# mem.net
KiCad netlist of a schematic drawn in Altium Designer
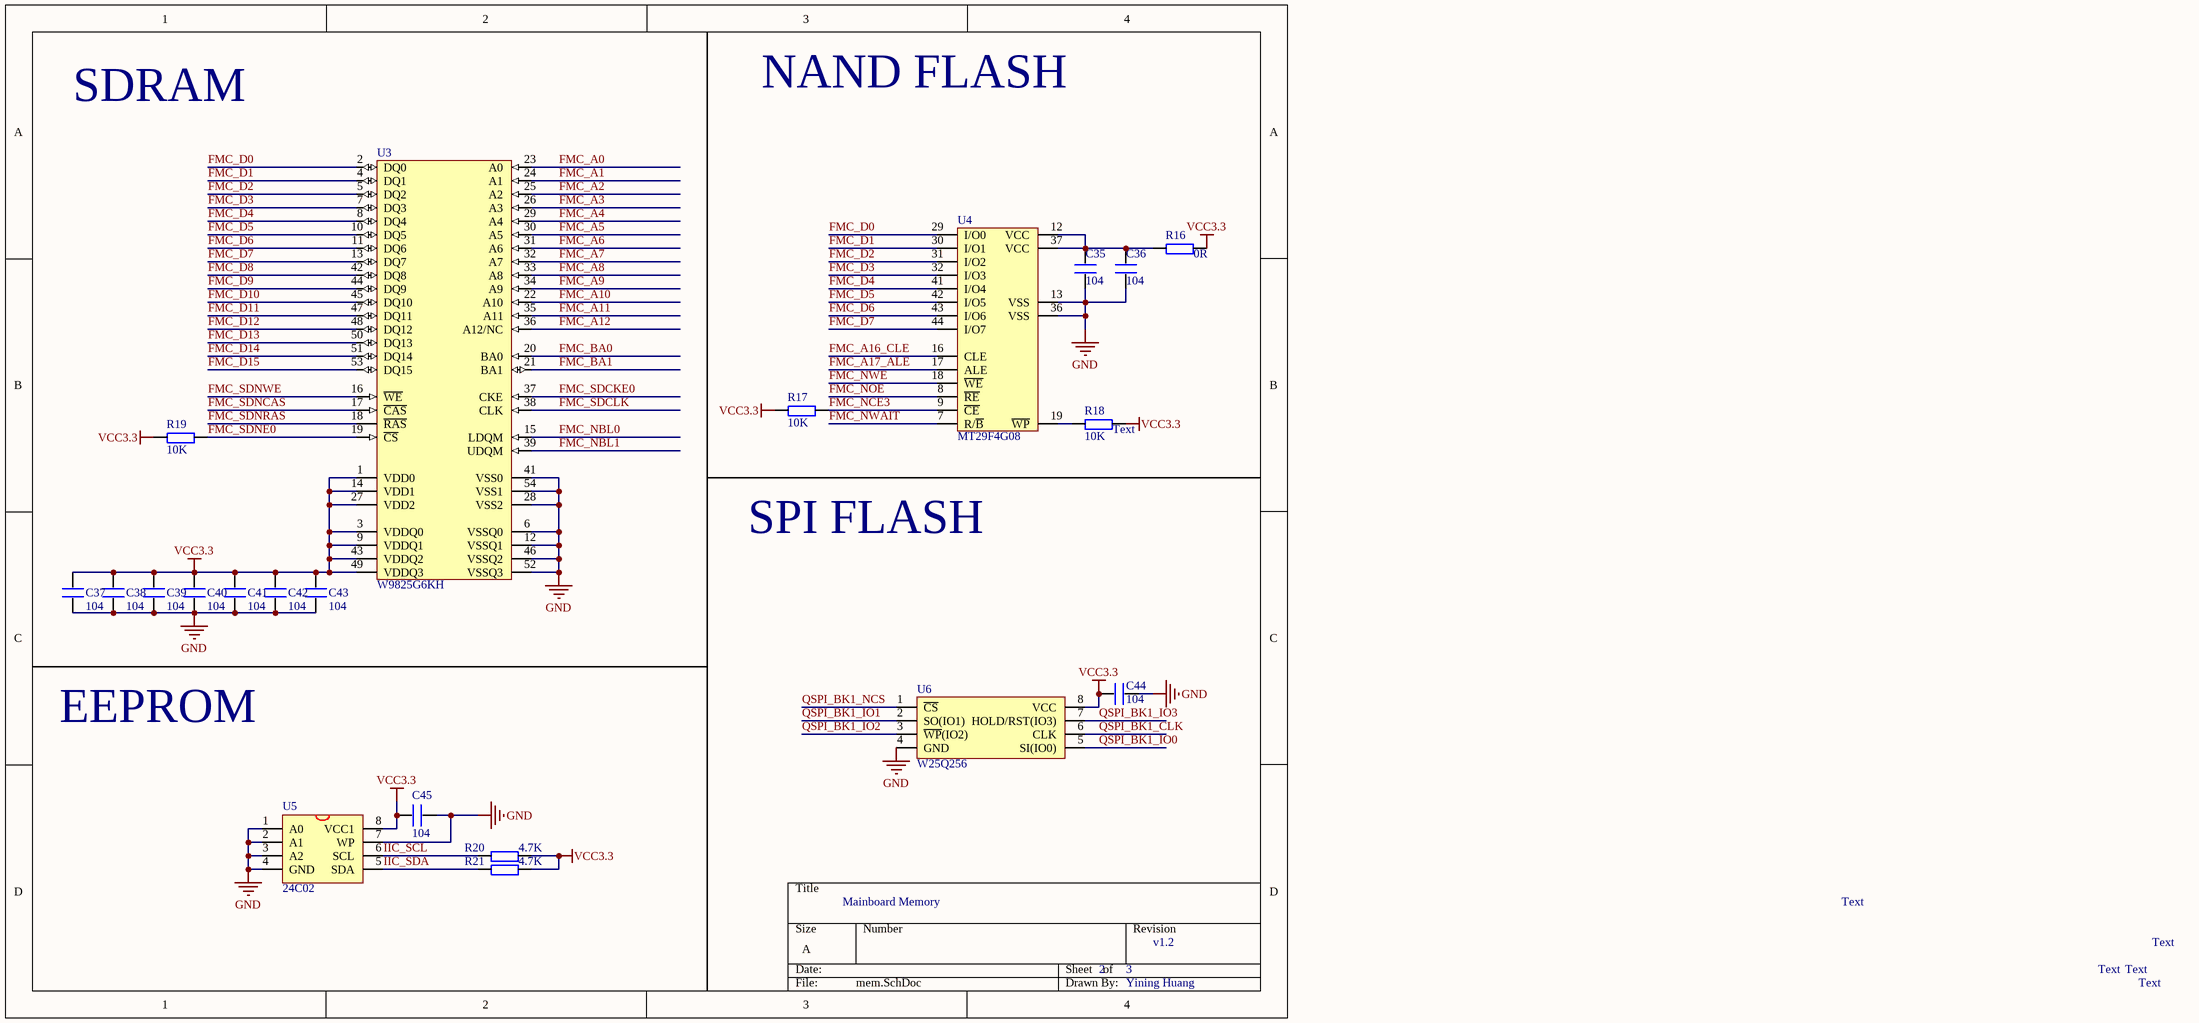
[diagram p0: mem.SchDoc]

(export (version "E")
  (design (tool "Eeschema 10.0.6"))
  (components
    (comp (ref "C35") (value "104") (footprint "0805") (libsource (lib "STM32F767核心板封装库") (part "C")))
    (comp (ref "C36") (value "104") (footprint "0805") (libsource (lib "STM32F767核心板封装库") (part "C")))
    (comp (ref "C37") (value "104") (footprint "0805") (libsource (lib "STM32F767核心板封装库") (part "C")))
    (comp (ref "C38") (value "104") (footprint "0805") (libsource (lib "STM32F767核心板封装库") (part "C")))
    (comp (ref "C39") (value "104") (footprint "0805") (libsource (lib "STM32F767核心板封装库") (part "C")))
    (comp (ref "C40") (value "104") (footprint "0805") (libsource (lib "STM32F767核心板封装库") (part "C")))
    (comp (ref "C41") (value "104") (footprint "0805") (libsource (lib "STM32F767核心板封装库") (part "C")))
    (comp (ref "C42") (value "104") (footprint "0805") (libsource (lib "STM32F767核心板封装库") (part "C")))
    (comp (ref "C43") (value "104") (footprint "0805") (libsource (lib "STM32F767核心板封装库") (part "C")))
    (comp (ref "C44") (value "104") (footprint "0805") (libsource (lib "STM32F767核心板封装库") (part "C")))
    (comp (ref "C45") (value "104") (footprint "0805") (libsource (lib "STM32F767核心板封装库") (part "C")))
    (comp (ref "R16") (value "0R") (footprint "0805") (libsource (lib "STM32F767核心板封装库") (part "R")))
    (comp (ref "R17") (value "10K") (footprint "0805") (libsource (lib "STM32F767核心板封装库") (part "R")))
    (comp (ref "R18") (value "10K") (footprint "0805") (libsource (lib "STM32F767核心板封装库") (part "R")))
    (comp (ref "R19") (value "10K") (footprint "0805") (libsource (lib "STM32F767核心板封装库") (part "R")))
    (comp (ref "R20") (value "4.7K") (footprint "0805") (libsource (lib "STM32F767核心板封装库") (part "R")))
    (comp (ref "R21") (value "4.7K") (footprint "0805") (libsource (lib "STM32F767核心板封装库") (part "R")))
    (comp (ref "U3")
      (value "W9825G6KH")
      (footprint "TSOP54")
      (description "32MB SDRAM")
      (libsource (lib "STM32F767核心板封装库") (part "IS42S16160B"))
    )
    (comp (ref "U4")
      (value "MT29F4G08")
      (footprint "TSOP48")
      (description "256MB NAND FLASH")
      (libsource (lib "STM32F767核心板封装库") (part "K9F2G08U0C"))
    )
    (comp (ref "U5")
      (value "24C02")
      (footprint "SOP-8")
      (description "EEPROM")
      (libsource (lib "STM32F767核心板封装库") (part "24C256"))
    )
    (comp (ref "U6")
      (value "W25Q256")
      (footprint "WSON8")
      (description "W25Q128")
      (libsource (lib "STM32F767核心板封装库") (part "W25Q128"))
    )
  )
  (nets
    (net (code "1") (name "/FMC_A0") (class "Default")
      (node (ref "U3") (pin "23") (pinfunction "A0_23") (pintype "input"))
    )
    (net (code "2") (name "/FMC_A1") (class "Default")
      (node (ref "U3") (pin "24") (pinfunction "A1_24") (pintype "input"))
    )
    (net (code "3") (name "/FMC_A2") (class "Default")
      (node (ref "U3") (pin "25") (pinfunction "A2_25") (pintype "input"))
    )
    (net (code "4") (name "/FMC_A3") (class "Default")
      (node (ref "U3") (pin "26") (pinfunction "A3_26") (pintype "input"))
    )
    (net (code "5") (name "/FMC_A4") (class "Default")
      (node (ref "U3") (pin "29") (pinfunction "A4_29") (pintype "input"))
    )
    (net (code "6") (name "/FMC_A5") (class "Default")
      (node (ref "U3") (pin "30") (pinfunction "A5_30") (pintype "input"))
    )
    (net (code "7") (name "/FMC_A6") (class "Default")
      (node (ref "U3") (pin "31") (pinfunction "A6_31") (pintype "input"))
    )
    (net (code "8") (name "/FMC_A7") (class "Default")
      (node (ref "U3") (pin "32") (pinfunction "A7_32") (pintype "input"))
    )
    (net (code "9") (name "/FMC_A8") (class "Default")
      (node (ref "U3") (pin "33") (pinfunction "A8_33") (pintype "input"))
    )
    (net (code "10") (name "/FMC_A9") (class "Default")
      (node (ref "U3") (pin "34") (pinfunction "A9_34") (pintype "input"))
    )
    (net (code "11") (name "/FMC_A10") (class "Default")
      (node (ref "U3") (pin "22") (pinfunction "A10_22") (pintype "input"))
    )
    (net (code "12") (name "/FMC_A11") (class "Default")
      (node (ref "U3") (pin "35") (pinfunction "A11_35") (pintype "input"))
    )
    (net (code "13") (name "/FMC_A12") (class "Default")
      (node (ref "U3") (pin "36") (pinfunction "A12/NC_36") (pintype "input"))
    )
    (net (code "14") (name "/FMC_A16_CLE") (class "Default")
      (node (ref "U4") (pin "16") (pinfunction "CLE_16") (pintype "passive"))
    )
    (net (code "15") (name "/FMC_A17_ALE") (class "Default")
      (node (ref "U4") (pin "17") (pinfunction "ALE_17") (pintype "passive"))
    )
    (net (code "16") (name "/FMC_BA0") (class "Default")
      (node (ref "U3") (pin "20") (pinfunction "BA0_20") (pintype "input"))
    )
    (net (code "17") (name "/FMC_BA1") (class "Default")
      (node (ref "U3") (pin "21") (pinfunction "BA1_21") (pintype "bidirectional"))
    )
    (net (code "18") (name "/FMC_D0") (class "Default")
      (node (ref "U3") (pin "2") (pinfunction "DQ0_2") (pintype "bidirectional"))
      (node (ref "U4") (pin "29") (pinfunction "I/O0_29") (pintype "passive"))
    )
    (net (code "19") (name "/FMC_D1") (class "Default")
      (node (ref "U3") (pin "4") (pinfunction "DQ1_4") (pintype "bidirectional"))
      (node (ref "U4") (pin "30") (pinfunction "I/O1_30") (pintype "passive"))
    )
    (net (code "20") (name "/FMC_D2") (class "Default")
      (node (ref "U3") (pin "5") (pinfunction "DQ2_5") (pintype "bidirectional"))
      (node (ref "U4") (pin "31") (pinfunction "I/O2_31") (pintype "passive"))
    )
    (net (code "21") (name "/FMC_D3") (class "Default")
      (node (ref "U3") (pin "7") (pinfunction "DQ3_7") (pintype "bidirectional"))
      (node (ref "U4") (pin "32") (pinfunction "I/O3_32") (pintype "passive"))
    )
    (net (code "22") (name "/FMC_D4") (class "Default")
      (node (ref "U3") (pin "8") (pinfunction "DQ4_8") (pintype "bidirectional"))
      (node (ref "U4") (pin "41") (pinfunction "I/O4_41") (pintype "passive"))
    )
    (net (code "23") (name "/FMC_D5") (class "Default")
      (node (ref "U3") (pin "10") (pinfunction "DQ5_10") (pintype "bidirectional"))
      (node (ref "U4") (pin "42") (pinfunction "I/O5_42") (pintype "passive"))
    )
    (net (code "24") (name "/FMC_D6") (class "Default")
      (node (ref "U3") (pin "11") (pinfunction "DQ6_11") (pintype "bidirectional"))
      (node (ref "U4") (pin "43") (pinfunction "I/O6_43") (pintype "passive"))
    )
    (net (code "25") (name "/FMC_D7") (class "Default")
      (node (ref "U3") (pin "13") (pinfunction "DQ7_13") (pintype "bidirectional"))
      (node (ref "U4") (pin "44") (pinfunction "I/O7_44") (pintype "passive"))
    )
    (net (code "26") (name "/FMC_D8") (class "Default")
      (node (ref "U3") (pin "42") (pinfunction "DQ8_42") (pintype "bidirectional"))
    )
    (net (code "27") (name "/FMC_D9") (class "Default")
      (node (ref "U3") (pin "44") (pinfunction "DQ9_44") (pintype "bidirectional"))
    )
    (net (code "28") (name "/FMC_D10") (class "Default")
      (node (ref "U3") (pin "45") (pinfunction "DQ10_45") (pintype "bidirectional"))
    )
    (net (code "29") (name "/FMC_D11") (class "Default")
      (node (ref "U3") (pin "47") (pinfunction "DQ11_47") (pintype "bidirectional"))
    )
    (net (code "30") (name "/FMC_D12") (class "Default")
      (node (ref "U3") (pin "48") (pinfunction "DQ12_48") (pintype "bidirectional"))
    )
    (net (code "31") (name "/FMC_D13") (class "Default")
      (node (ref "U3") (pin "50") (pinfunction "DQ13_50") (pintype "bidirectional"))
    )
    (net (code "32") (name "/FMC_D14") (class "Default")
      (node (ref "U3") (pin "51") (pinfunction "DQ14_51") (pintype "bidirectional"))
    )
    (net (code "33") (name "/FMC_D15") (class "Default")
      (node (ref "U3") (pin "53") (pinfunction "DQ15_53") (pintype "bidirectional"))
    )
    (net (code "34") (name "/FMC_NBL0") (class "Default")
      (node (ref "U3") (pin "15") (pinfunction "LDQM_15") (pintype "input"))
    )
    (net (code "35") (name "/FMC_NBL1") (class "Default")
      (node (ref "U3") (pin "39") (pinfunction "UDQM_39") (pintype "input"))
    )
    (net (code "36") (name "/FMC_NCE3") (class "Default")
      (node (ref "R17") (pin "2") (pintype "passive"))
      (node (ref "U4") (pin "9") (pinfunction "~{CE}_9") (pintype "passive"))
    )
    (net (code "37") (name "/FMC_NOE") (class "Default")
      (node (ref "U4") (pin "8") (pinfunction "~{RE}_8") (pintype "passive"))
    )
    (net (code "38") (name "/FMC_NWAIT") (class "Default")
      (node (ref "U4") (pin "7") (pinfunction "R/~{B}_7") (pintype "passive"))
    )
    (net (code "39") (name "/FMC_NWE") (class "Default")
      (node (ref "U4") (pin "18") (pinfunction "~{WE}_18") (pintype "passive"))
    )
    (net (code "40") (name "/FMC_SDCKE0") (class "Default")
      (node (ref "U3") (pin "37") (pinfunction "CKE_37") (pintype "input"))
    )
    (net (code "41") (name "/FMC_SDCLK") (class "Default")
      (node (ref "U3") (pin "38") (pinfunction "CLK_38") (pintype "input"))
    )
    (net (code "42") (name "/FMC_SDNCAS") (class "Default")
      (node (ref "U3") (pin "17") (pinfunction "~{CAS}_17") (pintype "input"))
    )
    (net (code "43") (name "/FMC_SDNE0") (class "Default")
      (node (ref "R19") (pin "2") (pintype "passive"))
      (node (ref "U3") (pin "19") (pinfunction "~{CS}_19") (pintype "input"))
    )
    (net (code "44") (name "/FMC_SDNRAS") (class "Default")
      (node (ref "U3") (pin "18") (pinfunction "~{RAS}_18") (pintype "passive"))
    )
    (net (code "45") (name "/FMC_SDNWE") (class "Default")
      (node (ref "U3") (pin "16") (pinfunction "~{WE}_16") (pintype "input"))
    )
    (net (code "46") (name "/IIC_SCL") (class "Default")
      (node (ref "R20") (pin "1") (pintype "passive"))
      (node (ref "U5") (pin "6") (pinfunction "SCL_6") (pintype "passive"))
    )
    (net (code "47") (name "/IIC_SDA") (class "Default")
      (node (ref "R21") (pin "1") (pintype "passive"))
      (node (ref "U5") (pin "5") (pinfunction "SDA_5") (pintype "passive"))
    )
    (net (code "48") (name "/QSPI_BK1_CLK") (class "Default")
      (node (ref "U6") (pin "6") (pinfunction "CLK_6") (pintype "passive"))
    )
    (net (code "49") (name "/QSPI_BK1_IO0") (class "Default")
      (node (ref "U6") (pin "5") (pinfunction "SI(IO0)_5") (pintype "power_in"))
    )
    (net (code "50") (name "/QSPI_BK1_IO1") (class "Default")
      (node (ref "U6") (pin "2") (pinfunction "SO(IO1)_2") (pintype "passive"))
    )
    (net (code "51") (name "/QSPI_BK1_IO2") (class "Default")
      (node (ref "U6") (pin "3") (pinfunction "~{WP}(IO2)_3") (pintype "passive"))
    )
    (net (code "52") (name "/QSPI_BK1_IO3") (class "Default")
      (node (ref "U6") (pin "7") (pinfunction "HOLD/RST(IO3)_7") (pintype "power_in"))
    )
    (net (code "53") (name "/QSPI_BK1_NCS") (class "Default")
      (node (ref "U6") (pin "1") (pinfunction "~{CS}_1") (pintype "passive"))
    )
    (net (code "54") (name "GND") (class "Default")
      (node (ref "C35") (pin "1") (pintype "passive"))
      (node (ref "C36") (pin "1") (pintype "passive"))
      (node (ref "C37") (pin "1") (pintype "passive"))
      (node (ref "C38") (pin "1") (pintype "passive"))
      (node (ref "C39") (pin "1") (pintype "passive"))
      (node (ref "C40") (pin "1") (pintype "passive"))
      (node (ref "C41") (pin "1") (pintype "passive"))
      (node (ref "C42") (pin "1") (pintype "passive"))
      (node (ref "C43") (pin "1") (pintype "passive"))
      (node (ref "C44") (pin "2") (pintype "passive"))
      (node (ref "C45") (pin "2") (pintype "passive"))
      (node (ref "U3") (pin "12") (pinfunction "VSSQ1_12") (pintype "power_in"))
      (node (ref "U3") (pin "28") (pinfunction "VSS2_28") (pintype "power_in"))
      (node (ref "U3") (pin "41") (pinfunction "VSS0_41") (pintype "power_in"))
      (node (ref "U3") (pin "46") (pinfunction "VSSQ2_46") (pintype "power_in"))
      (node (ref "U3") (pin "52") (pinfunction "VSSQ3_52") (pintype "power_in"))
      (node (ref "U3") (pin "54") (pinfunction "VSS1_54") (pintype "power_in"))
      (node (ref "U3") (pin "6") (pinfunction "VSSQ0_6") (pintype "power_in"))
      (node (ref "U4") (pin "13") (pinfunction "VSS_13") (pintype "passive"))
      (node (ref "U4") (pin "36") (pinfunction "VSS_36") (pintype "passive"))
      (node (ref "U5") (pin "1") (pinfunction "A0_1") (pintype "passive"))
      (node (ref "U5") (pin "2") (pinfunction "A1_2") (pintype "passive"))
      (node (ref "U5") (pin "3") (pinfunction "A2_3") (pintype "passive"))
      (node (ref "U5") (pin "4") (pinfunction "GND_4") (pintype "passive"))
      (node (ref "U5") (pin "7") (pinfunction "WP_7") (pintype "passive"))
      (node (ref "U6") (pin "4") (pinfunction "GND_4") (pintype "passive"))
    )
    (net (code "55") (name "Net-(C35-Pad2)") (class "Default")
      (node (ref "C35") (pin "2") (pintype "passive"))
      (node (ref "C36") (pin "2") (pintype "passive"))
      (node (ref "R16") (pin "1") (pintype "passive"))
      (node (ref "U4") (pin "12") (pinfunction "VCC_12") (pintype "passive"))
      (node (ref "U4") (pin "37") (pinfunction "VCC_37") (pintype "passive"))
    )
    (net (code "56") (name "Net-(U4-~{WP})") (class "Default")
      (node (ref "R18") (pin "1") (pintype "passive"))
      (node (ref "U4") (pin "19") (pinfunction "~{WP}_19") (pintype "passive"))
    )
    (net (code "57") (name "VCC3.3") (class "Default")
      (node (ref "C37") (pin "2") (pintype "passive"))
      (node (ref "C38") (pin "2") (pintype "passive"))
      (node (ref "C39") (pin "2") (pintype "passive"))
      (node (ref "C40") (pin "2") (pintype "passive"))
      (node (ref "C41") (pin "2") (pintype "passive"))
      (node (ref "C42") (pin "2") (pintype "passive"))
      (node (ref "C43") (pin "2") (pintype "passive"))
      (node (ref "C44") (pin "1") (pintype "passive"))
      (node (ref "C45") (pin "1") (pintype "passive"))
      (node (ref "R16") (pin "2") (pintype "passive"))
      (node (ref "R17") (pin "1") (pintype "passive"))
      (node (ref "R18") (pin "2") (pintype "passive"))
      (node (ref "R19") (pin "1") (pintype "passive"))
      (node (ref "R20") (pin "2") (pintype "passive"))
      (node (ref "R21") (pin "2") (pintype "passive"))
      (node (ref "U3") (pin "1") (pinfunction "VDD0_1") (pintype "power_in"))
      (node (ref "U3") (pin "14") (pinfunction "VDD1_14") (pintype "power_in"))
      (node (ref "U3") (pin "27") (pinfunction "VDD2_27") (pintype "power_in"))
      (node (ref "U3") (pin "3") (pinfunction "VDDQ0_3") (pintype "power_in"))
      (node (ref "U3") (pin "43") (pinfunction "VDDQ2_43") (pintype "power_in"))
      (node (ref "U3") (pin "49") (pinfunction "VDDQ3_49") (pintype "power_in"))
      (node (ref "U3") (pin "9") (pinfunction "VDDQ1_9") (pintype "power_in"))
      (node (ref "U5") (pin "8") (pinfunction "VCC1_8") (pintype "passive"))
      (node (ref "U6") (pin "8") (pinfunction "VCC_8") (pintype "passive"))
    )
  )
)
